# robot_mini_r1.net
KiCad netlist of a schematic drawn in EAGLE
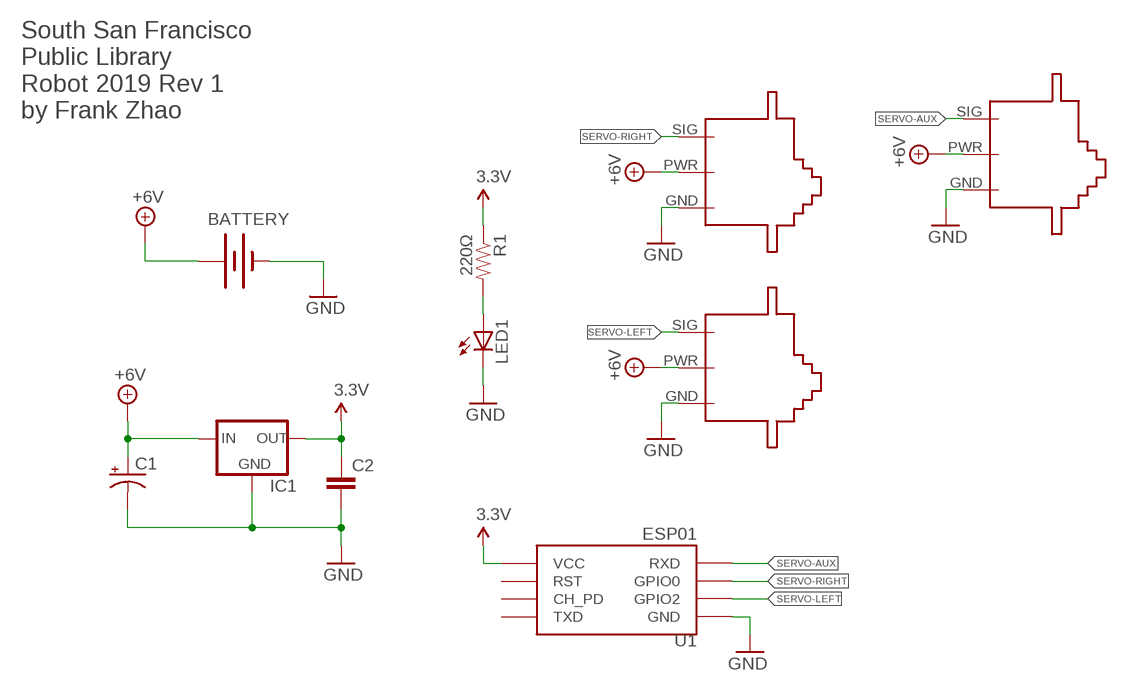
[diagram p0: schematic, sheet 1]

(export (version "E")
  (design (tool "Eeschema 10.0.6"))
  (components
    (comp (ref "BATTERY")
      (value "BATTERY-WIRE-CONN")
      (footprint "eagle-import:BATT-WIRE-CONN")
      (libsource (lib "eagle-import") (part "BATTERY-WIRE-CONN"))
    )
    (comp (ref "C1")
      (value "CAP_POLPTH1")
      (footprint "eagle-import:CPOL-RADIAL-100UF-25V")
      (libsource (lib "eagle-import") (part "CAP_POLPTH1"))
    )
    (comp (ref "C2")
      (value "CAPPTH")
      (footprint "eagle-import:CAP-PTH-SMALL")
      (libsource (lib "eagle-import") (part "CAPPTH"))
    )
    (comp (ref "IC1")
      (value "V_REG_78XXTO-92")
      (footprint "eagle-import:TO-92")
      (libsource (lib "eagle-import") (part "V_REG_78XXTO-92"))
    )
    (comp (ref "LED1")
      (value "LED5MM")
      (footprint "eagle-import:LED5MM")
      (libsource (lib "eagle-import") (part "LED5MM"))
    )
    (comp (ref "M1")
      (value "SERVO-FLIPPED")
      (footprint "eagle-import:SERVO-FLIPPED")
      (libsource (lib "eagle-import") (part "SERVO-FLIPPED"))
    )
    (comp (ref "M2")
      (value "SERVO-1")
      (footprint "eagle-import:SERVO")
      (libsource (lib "eagle-import") (part "SERVO-1"))
    )
    (comp (ref "M3")
      (value "SERVO-1")
      (footprint "eagle-import:SERVO")
      (libsource (lib "eagle-import") (part "SERVO-1"))
    )
    (comp (ref "R1")
      (value "220Ω")
      (footprint "eagle-import:AXIAL-0.3-NOVAL")
      (libsource (lib "eagle-import") (part "RESISTORAXIAL-0.3-NOVAL"))
    )
    (comp (ref "U$9")
      (value "TEXT-INFO-INVISIBLE")
      (footprint "eagle-import:TEXT-INFO-INVISIBLE")
      (libsource (lib "eagle-import") (part "TEXT-INFO-INVISIBLE"))
    )
    (comp (ref "U1")
      (value "ESP01")
      (footprint "eagle-import:ESP01")
      (libsource (lib "eagle-import") (part "ESP01"))
    )
  )
  (nets
    (net (code "1") (name "+6V") (class "Default")
      (node (ref "BATTERY") (pin "POS") (pinfunction "+_POS") (pintype "power_in"))
      (node (ref "C1") (pin "1") (pinfunction "+_1") (pintype "passive"))
      (node (ref "IC1") (pin "2") (pinfunction "IN_2") (pintype "input"))
      (node (ref "M1") (pin "PWR") (pinfunction "PWR_PWR") (pintype "bidirectional"))
      (node (ref "M2") (pin "PWR") (pinfunction "PWR_PWR") (pintype "bidirectional"))
      (node (ref "M3") (pin "PWR") (pinfunction "PWR_PWR") (pintype "bidirectional"))
    )
    (net (code "2") (name "3.3V") (class "Default")
      (node (ref "C2") (pin "1") (pinfunction "1_1") (pintype "passive"))
      (node (ref "IC1") (pin "3") (pinfunction "OUT_3") (pintype "output"))
      (node (ref "R1") (pin "P$1") (pinfunction "1_P$1") (pintype "passive"))
      (node (ref "U1") (pin "VCC") (pinfunction "VCC_VCC") (pintype "bidirectional"))
    )
    (net (code "3") (name "GND") (class "Default")
      (node (ref "BATTERY") (pin "NEG") (pinfunction "-_NEG") (pintype "power_in"))
      (node (ref "C1") (pin "2") (pinfunction "-_2") (pintype "passive"))
      (node (ref "C2") (pin "2") (pinfunction "2_2") (pintype "passive"))
      (node (ref "IC1") (pin "1") (pinfunction "GND_1") (pintype "input"))
      (node (ref "LED1") (pin "K") (pinfunction "C_K") (pintype "passive"))
      (node (ref "M1") (pin "GND") (pinfunction "GND_GND") (pintype "bidirectional"))
      (node (ref "M2") (pin "GND") (pinfunction "GND_GND") (pintype "bidirectional"))
      (node (ref "M3") (pin "GND") (pinfunction "GND_GND") (pintype "bidirectional"))
      (node (ref "U1") (pin "GND") (pinfunction "GND_GND") (pintype "bidirectional"))
    )
    (net (code "4") (name "Net-(R1-2)") (class "Default")
      (node (ref "LED1") (pin "A") (pinfunction "A_A") (pintype "passive"))
      (node (ref "R1") (pin "P$2") (pinfunction "2_P$2") (pintype "passive"))
    )
    (net (code "5") (name "SERVO-AUX") (class "Default")
      (node (ref "M3") (pin "SIG") (pinfunction "SIG_SIG") (pintype "bidirectional"))
      (node (ref "U1") (pin "RX") (pinfunction "RXD_RX") (pintype "bidirectional"))
    )
    (net (code "6") (name "SERVO-LEFT") (class "Default")
      (node (ref "M1") (pin "SIG") (pinfunction "SIG_SIG") (pintype "bidirectional"))
      (node (ref "U1") (pin "GPIO2") (pinfunction "GPIO2_GPIO2") (pintype "bidirectional"))
    )
    (net (code "7") (name "SERVO-RIGHT") (class "Default")
      (node (ref "M2") (pin "SIG") (pinfunction "SIG_SIG") (pintype "bidirectional"))
      (node (ref "U1") (pin "GPIO0") (pinfunction "GPIO0_GPIO0") (pintype "bidirectional"))
    )
    (net (code "8") (name "unconnected-(U1-PadCH_PD)") (class "Default")
      (node (ref "U1") (pin "CH_PD") (pinfunction "CH_PD_CH_PD") (pintype "bidirectional"))
    )
    (net (code "9") (name "unconnected-(U1-PadRST)") (class "Default")
      (node (ref "U1") (pin "RST") (pinfunction "RST_RST") (pintype "bidirectional"))
    )
    (net (code "10") (name "unconnected-(U1-TXD-PadTX)") (class "Default")
      (node (ref "U1") (pin "TX") (pinfunction "TXD_TX") (pintype "bidirectional"))
    )
  )
)
